# 12-20.net
KiCad netlist of a schematic drawn in EAGLE
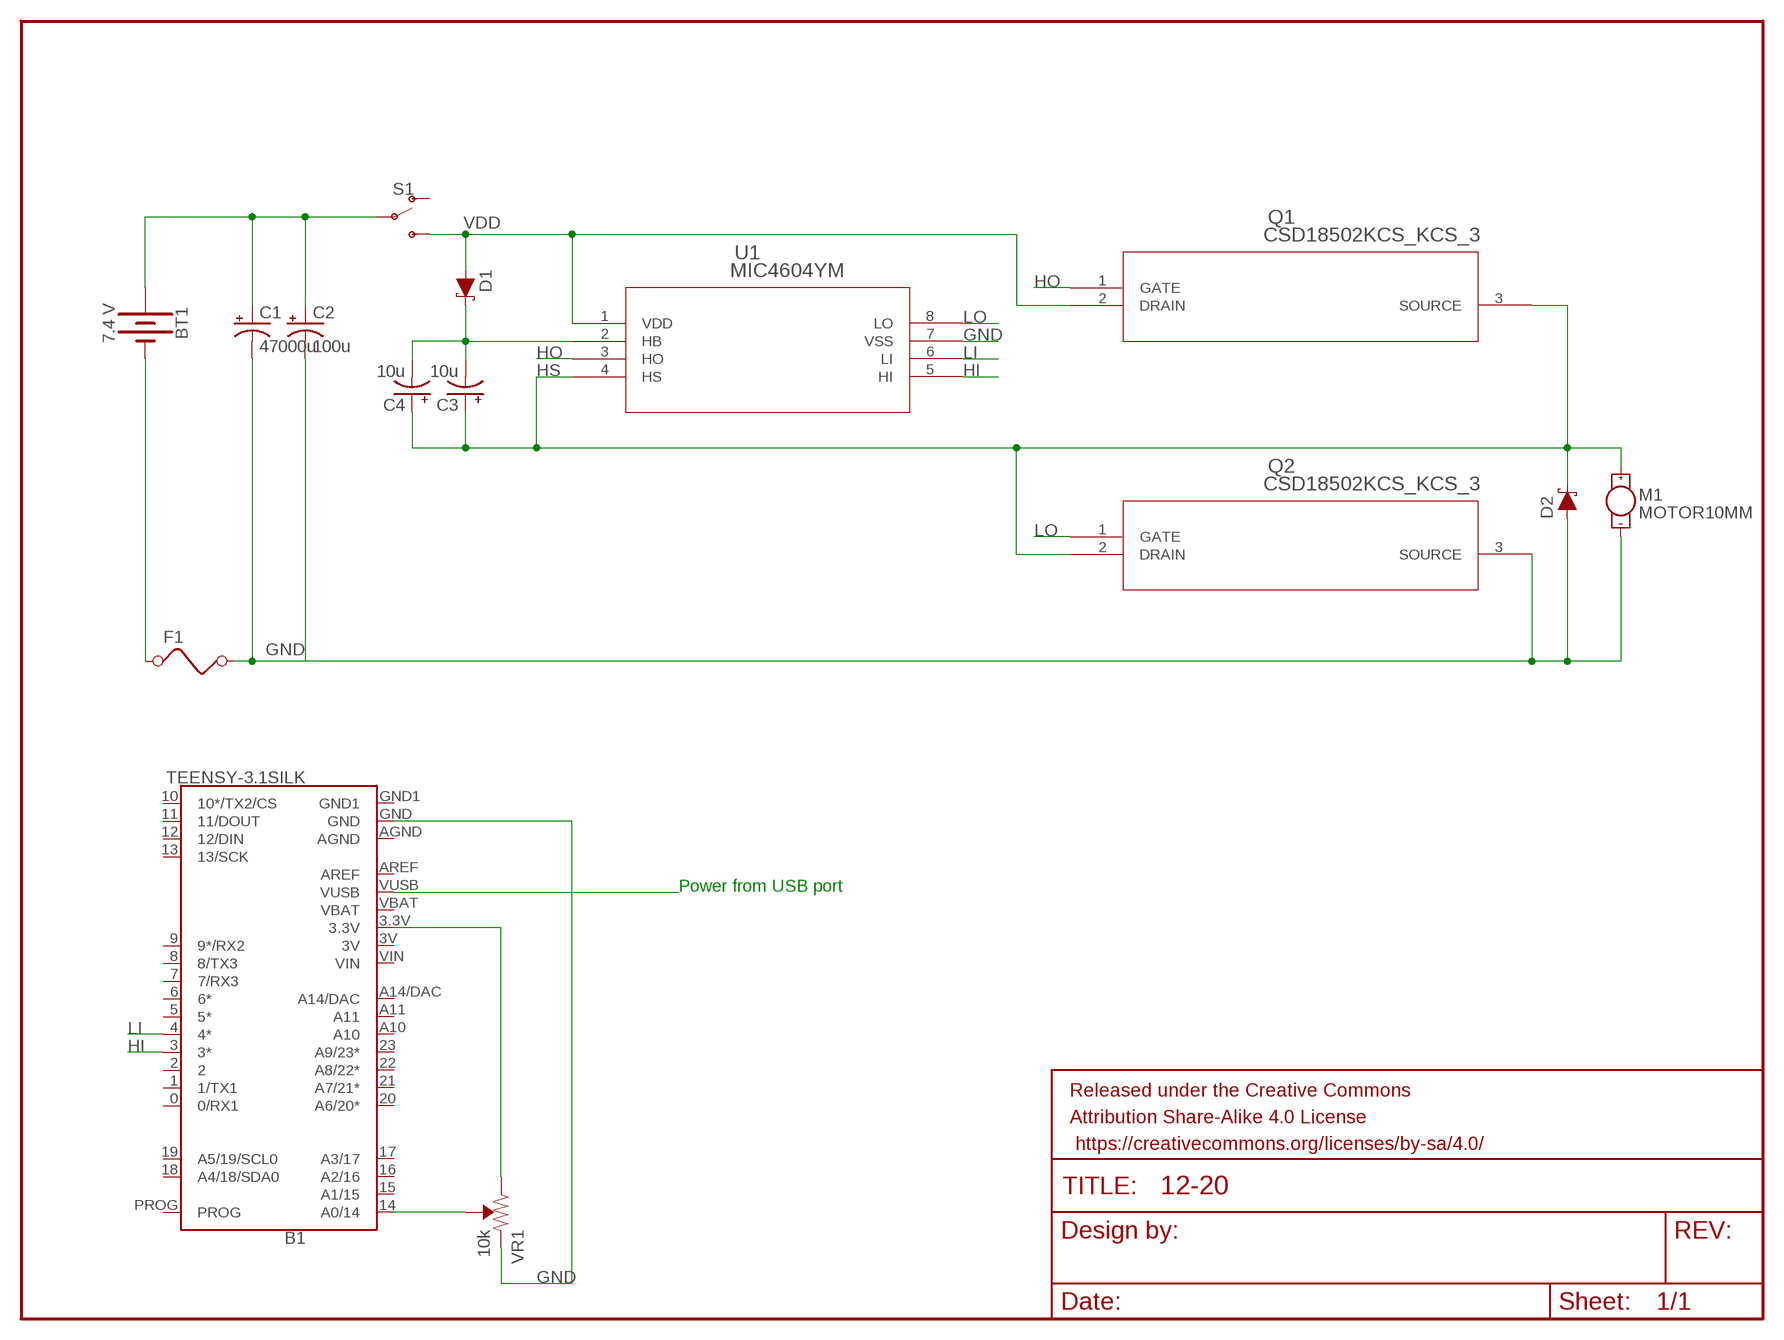
[diagram p0: schematic, sheet 1]

(export (version "E")
  (design (tool "Eeschema 10.0.6"))
  (components
    (comp (ref "B1")
      (value "TEENSY-3.1SILK")
      (footprint "eagle-import:TEENSY-3.1")
      (libsource (lib "eagle-import") (part "TEENSY-3.1SILK"))
    )
    (comp (ref "BT1")
      (value "7.4 V")
      (footprint "eagle-import:BATTERY-AA")
      (libsource (lib "eagle-import") (part "BATTERY-AA"))
    )
    (comp (ref "C1")
      (value "47000u")
      (footprint "eagle-import:EB35D")
      (libsource (lib "eagle-import") (part "CPOL-USE10-35"))
    )
    (comp (ref "C2")
      (value "100u")
      (footprint "eagle-import:EB35D")
      (libsource (lib "eagle-import") (part "CPOL-USE10-35"))
    )
    (comp (ref "C3")
      (value "10u")
      (footprint "eagle-import:EB35D")
      (libsource (lib "eagle-import") (part "CPOL-USE10-35"))
    )
    (comp (ref "C4")
      (value "10u")
      (footprint "eagle-import:EB35D")
      (libsource (lib "eagle-import") (part "CPOL-USE10-35"))
    )
    (comp (ref "D1")
      (value "DIODE-SCHOTTKY-ZLLS500")
      (footprint "eagle-import:SOT23-3")
      (libsource (lib "eagle-import") (part "DIODE-SCHOTTKY-ZLLS500"))
    )
    (comp (ref "D2")
      (value "DIODE-SCHOTTKY-ZLLS500")
      (footprint "eagle-import:SOT23-3")
      (libsource (lib "eagle-import") (part "DIODE-SCHOTTKY-ZLLS500"))
    )
    (comp (ref "F1")
      (value "FUSE")
      (footprint "eagle-import:FUSE")
      (libsource (lib "eagle-import") (part "FUSE"))
    )
    (comp (ref "FRAME1")
      (value "FRAME-LETTER")
      (footprint "eagle-import:CREATIVE_COMMONS")
      (libsource (lib "eagle-import") (part "FRAME-LETTER"))
    )
    (comp (ref "M1")
      (value "MOTOR10MM")
      (footprint "eagle-import:VIBE-MOTOR-10MM")
      (libsource (lib "eagle-import") (part "MOTOR10MM"))
    )
    (comp (ref "Q1")
      (value "CSD18502KCS_KCS_3")
      (footprint "eagle-import:KCS3")
      (fields (field (name "MANUFACTURER_PART_NUMBER") "csd18502kcs_kcs_3"))
      (libsource (lib "eagle-import") (part "CSD18502KCS_KCS_3"))
    )
    (comp (ref "Q2")
      (value "CSD18502KCS_KCS_3")
      (footprint "eagle-import:KCS3")
      (fields (field (name "MANUFACTURER_PART_NUMBER") "csd18502kcs_kcs_3"))
      (libsource (lib "eagle-import") (part "CSD18502KCS_KCS_3"))
    )
    (comp (ref "S1")
      (value "SWITCH-SPDT-PTH-11.6X4.0MM")
      (footprint "eagle-import:SWITCH_SPDT_PTH_11.6X4.0MM")
      (libsource (lib "eagle-import") (part "SWITCH-SPDT-PTH-11.6X4.0MM"))
    )
    (comp (ref "U1")
      (value "MIC4604YM")
      (footprint "eagle-import:SOIC-8_M")
      (fields (field (name "MANUFACTURER_PART_NUMBER") "mic4604ym"))
      (libsource (lib "eagle-import") (part "MIC4604YM"))
    )
    (comp (ref "VR1")
      (value "10k")
      (footprint "eagle-import:TRIMPOT-PTH-3386U")
      (libsource (lib "eagle-import") (part "TRIMPOT-PTH-10MM-KNOB-1/2W-10%"))
    )
  )
  (nets
    (net (code "1") (name "/3V") (class "Default")
      (node (ref "B1") (pin "3V") (pinfunction "3V_3V") (pintype "power_in"))
    )
    (net (code "2") (name "/AGND") (class "Default")
      (node (ref "B1") (pin "AGND") (pinfunction "AGND_AGND") (pintype "power_in"))
    )
    (net (code "3") (name "/GND") (class "Default")
      (node (ref "B1") (pin "GND") (pinfunction "GND_GND") (pintype "power_in"))
      (node (ref "C1") (pin "-") (pinfunction "-_-") (pintype "passive"))
      (node (ref "C2") (pin "-") (pinfunction "-_-") (pintype "passive"))
      (node (ref "D2") (pin "1") (pinfunction "A_1") (pintype "passive"))
      (node (ref "F1") (pin "2") (pinfunction "2_2") (pintype "passive"))
      (node (ref "M1") (pin "-") (pinfunction "-_-") (pintype "bidirectional"))
      (node (ref "Q2") (pin "3") (pinfunction "SOURCE_3") (pintype "passive"))
      (node (ref "U1") (pin "7") (pinfunction "VSS_7") (pintype "power_in"))
      (node (ref "VR1") (pin "1") (pinfunction "CCW_1") (pintype "passive"))
    )
    (net (code "4") (name "/GND1") (class "Default")
      (node (ref "B1") (pin "GND1") (pinfunction "GND1_GND1") (pintype "power_in"))
    )
    (net (code "5") (name "/HI") (class "Default")
      (node (ref "B1") (pin "3") (pinfunction "3*_3") (pintype "bidirectional"))
      (node (ref "U1") (pin "5") (pinfunction "HI_5") (pintype "input"))
    )
    (net (code "6") (name "/HO") (class "Default")
      (node (ref "Q1") (pin "1") (pinfunction "GATE_1") (pintype "passive"))
      (node (ref "U1") (pin "3") (pinfunction "HO_3") (pintype "output"))
    )
    (net (code "7") (name "/HS") (class "Default")
      (node (ref "C3") (pin "+") (pinfunction "+_+") (pintype "passive"))
      (node (ref "C4") (pin "+") (pinfunction "+_+") (pintype "passive"))
      (node (ref "D2") (pin "3") (pinfunction "C_3") (pintype "passive"))
      (node (ref "M1") (pin "+") (pinfunction "+_+") (pintype "bidirectional"))
      (node (ref "Q1") (pin "3") (pinfunction "SOURCE_3") (pintype "passive"))
      (node (ref "Q2") (pin "2") (pinfunction "DRAIN_2") (pintype "passive"))
      (node (ref "U1") (pin "4") (pinfunction "HS_4") (pintype "passive"))
    )
    (net (code "8") (name "/LI") (class "Default")
      (node (ref "B1") (pin "4") (pinfunction "4*_4") (pintype "bidirectional"))
      (node (ref "U1") (pin "6") (pinfunction "LI_6") (pintype "input"))
    )
    (net (code "9") (name "/LO") (class "Default")
      (node (ref "Q2") (pin "1") (pinfunction "GATE_1") (pintype "passive"))
      (node (ref "U1") (pin "8") (pinfunction "LO_8") (pintype "output"))
    )
    (net (code "10") (name "/VBAT") (class "Default")
      (node (ref "B1") (pin "VBAT") (pinfunction "VBAT_VBAT") (pintype "power_in"))
    )
    (net (code "11") (name "/VDD") (class "Default")
      (node (ref "D1") (pin "1") (pinfunction "A_1") (pintype "passive"))
      (node (ref "Q1") (pin "2") (pinfunction "DRAIN_2") (pintype "passive"))
      (node (ref "S1") (pin "3") (pinfunction "S_3") (pintype "passive"))
      (node (ref "U1") (pin "1") (pinfunction "VDD_1") (pintype "power_in"))
    )
    (net (code "12") (name "/VIN") (class "Default")
      (node (ref "B1") (pin "VIN") (pinfunction "VIN_VIN") (pintype "power_in"))
    )
    (net (code "13") (name "Net-(B1-A0{slash}14)") (class "Default")
      (node (ref "B1") (pin "14") (pinfunction "A0/14_14") (pintype "bidirectional"))
      (node (ref "VR1") (pin "2") (pinfunction "WIPER_2") (pintype "passive"))
    )
    (net (code "14") (name "Net-(BT1-+)") (class "Default")
      (node (ref "BT1") (pin "PWR@1") (pinfunction "+_PWR@1") (pintype "power_in"))
      (node (ref "C1") (pin "+") (pinfunction "+_+") (pintype "passive"))
      (node (ref "C2") (pin "+") (pinfunction "+_+") (pintype "passive"))
      (node (ref "S1") (pin "2") (pinfunction "P_2") (pintype "passive"))
    )
    (net (code "15") (name "Net-(BT1--)") (class "Default")
      (node (ref "BT1") (pin "GND@1") (pinfunction "-_GND@1") (pintype "power_in"))
      (node (ref "F1") (pin "1") (pinfunction "1_1") (pintype "passive"))
    )
    (net (code "16") (name "Net-(D1-C)") (class "Default")
      (node (ref "C3") (pin "-") (pinfunction "-_-") (pintype "passive"))
      (node (ref "C4") (pin "-") (pinfunction "-_-") (pintype "passive"))
      (node (ref "D1") (pin "3") (pinfunction "C_3") (pintype "passive"))
      (node (ref "U1") (pin "2") (pinfunction "HB_2") (pintype "passive"))
    )
    (net (code "17") (name "Net-(VR1-CW)") (class "Default")
      (node (ref "B1") (pin "3.3V") (pinfunction "3.3V_3.3V") (pintype "power_in"))
      (node (ref "VR1") (pin "3") (pinfunction "CW_3") (pintype "passive"))
    )
    (net (code "18") (name "unconnected-(B1-0{slash}RX1-Pad0)") (class "Default")
      (node (ref "B1") (pin "0") (pinfunction "0/RX1_0") (pintype "bidirectional"))
    )
    (net (code "19") (name "unconnected-(B1-1{slash}TX1-Pad1)") (class "Default")
      (node (ref "B1") (pin "1") (pinfunction "1/TX1_1") (pintype "bidirectional"))
    )
    (net (code "20") (name "unconnected-(B1-5*-Pad5)") (class "Default")
      (node (ref "B1") (pin "5") (pinfunction "5*_5") (pintype "bidirectional"))
    )
    (net (code "21") (name "unconnected-(B1-6*-Pad6)") (class "Default")
      (node (ref "B1") (pin "6") (pinfunction "6*_6") (pintype "bidirectional"))
    )
    (net (code "22") (name "unconnected-(B1-7{slash}RX3-Pad7)") (class "Default")
      (node (ref "B1") (pin "7") (pinfunction "7/RX3_7") (pintype "bidirectional"))
    )
    (net (code "23") (name "unconnected-(B1-8{slash}TX3-Pad8)") (class "Default")
      (node (ref "B1") (pin "8") (pinfunction "8/TX3_8") (pintype "bidirectional"))
    )
    (net (code "24") (name "unconnected-(B1-9*{slash}RX2-Pad9)") (class "Default")
      (node (ref "B1") (pin "9") (pinfunction "9*/RX2_9") (pintype "bidirectional"))
    )
    (net (code "25") (name "unconnected-(B1-10*{slash}TX2{slash}CS-Pad10)") (class "Default")
      (node (ref "B1") (pin "10") (pinfunction "10*/TX2/CS_10") (pintype "bidirectional"))
    )
    (net (code "26") (name "unconnected-(B1-11{slash}DOUT-Pad11)") (class "Default")
      (node (ref "B1") (pin "11") (pinfunction "11/DOUT_11") (pintype "bidirectional"))
    )
    (net (code "27") (name "unconnected-(B1-12{slash}DIN-Pad12)") (class "Default")
      (node (ref "B1") (pin "12") (pinfunction "12/DIN_12") (pintype "bidirectional"))
    )
    (net (code "28") (name "unconnected-(B1-13{slash}SCK-Pad13)") (class "Default")
      (node (ref "B1") (pin "13") (pinfunction "13/SCK_13") (pintype "bidirectional"))
    )
    (net (code "29") (name "unconnected-(B1-A1{slash}15-Pad15)") (class "Default")
      (node (ref "B1") (pin "15") (pinfunction "A1/15_15") (pintype "bidirectional"))
    )
    (net (code "30") (name "unconnected-(B1-A2{slash}16-Pad16)") (class "Default")
      (node (ref "B1") (pin "16") (pinfunction "A2/16_16") (pintype "bidirectional"))
    )
    (net (code "31") (name "unconnected-(B1-A3{slash}17-Pad17)") (class "Default")
      (node (ref "B1") (pin "17") (pinfunction "A3/17_17") (pintype "bidirectional"))
    )
    (net (code "32") (name "unconnected-(B1-A4{slash}18{slash}SDA0-Pad18)") (class "Default")
      (node (ref "B1") (pin "18") (pinfunction "A4/18/SDA0_18") (pintype "bidirectional"))
    )
    (net (code "33") (name "unconnected-(B1-A5{slash}19{slash}SCL0-Pad19)") (class "Default")
      (node (ref "B1") (pin "19") (pinfunction "A5/19/SCL0_19") (pintype "bidirectional"))
    )
    (net (code "34") (name "unconnected-(B1-A6{slash}20*-Pad20)") (class "Default")
      (node (ref "B1") (pin "20") (pinfunction "A6/20*_20") (pintype "bidirectional"))
    )
    (net (code "35") (name "unconnected-(B1-A7{slash}21*-Pad21)") (class "Default")
      (node (ref "B1") (pin "21") (pinfunction "A7/21*_21") (pintype "bidirectional"))
    )
    (net (code "36") (name "unconnected-(B1-A8{slash}22*-Pad22)") (class "Default")
      (node (ref "B1") (pin "22") (pinfunction "A8/22*_22") (pintype "bidirectional"))
    )
    (net (code "37") (name "unconnected-(B1-A9{slash}23*-Pad23)") (class "Default")
      (node (ref "B1") (pin "23") (pinfunction "A9/23*_23") (pintype "bidirectional"))
    )
    (net (code "38") (name "unconnected-(B1-Pad2)") (class "Default")
      (node (ref "B1") (pin "2") (pinfunction "2_2") (pintype "bidirectional"))
    )
    (net (code "39") (name "unconnected-(B1-PadA10)") (class "Default")
      (node (ref "B1") (pin "A10") (pinfunction "A10_A10") (pintype "bidirectional"))
    )
    (net (code "40") (name "unconnected-(B1-PadA11)") (class "Default")
      (node (ref "B1") (pin "A11") (pinfunction "A11_A11") (pintype "bidirectional"))
    )
    (net (code "41") (name "unconnected-(B1-PadA14{slash}DAC)") (class "Default")
      (node (ref "B1") (pin "A14/DAC") (pinfunction "A14/DAC_A14/DAC") (pintype "bidirectional"))
    )
    (net (code "42") (name "unconnected-(B1-PadAREF)") (class "Default")
      (node (ref "B1") (pin "AREF") (pinfunction "AREF_AREF") (pintype "bidirectional"))
    )
    (net (code "43") (name "unconnected-(B1-PadPROG)") (class "Default")
      (node (ref "B1") (pin "PROG") (pinfunction "PROG_PROG") (pintype "bidirectional"))
    )
    (net (code "44") (name "unconnected-(B1-PadVUSB)") (class "Default")
      (node (ref "B1") (pin "VUSB") (pinfunction "VUSB_VUSB") (pintype "power_in"))
    )
    (net (code "45") (name "unconnected-(S1-O-Pad1)") (class "Default")
      (node (ref "S1") (pin "1") (pinfunction "O_1") (pintype "passive"))
    )
  )
)
